# pressure.net
KiCad netlist of a schematic drawn in Altium Designer
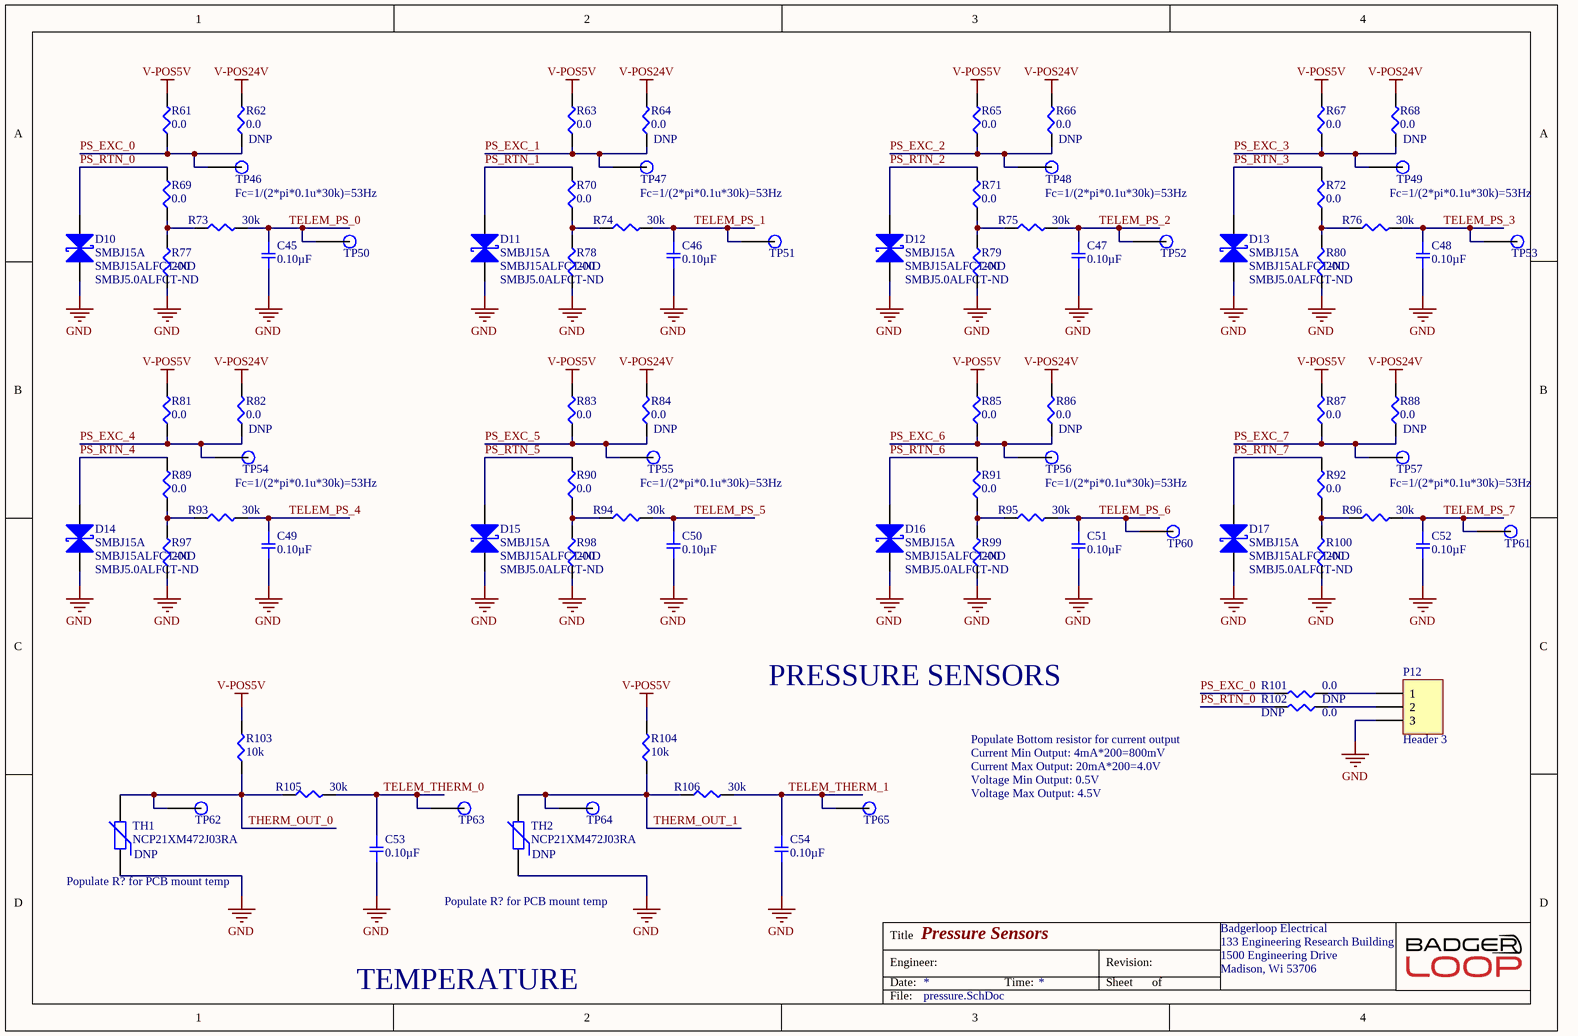
[diagram p0: pressure.SchDoc]

(export (version "E")
  (design (tool "Eeschema 10.0.6"))
  (components
    (comp (ref "C45")
      (value "0.10µF")
      (footprint "SMD-0805C")
      (description "CAP CER 0.1UF 25V X7R 0805")
      (fields
        (field (name "DIGI-KEY PART NUMBER") "490-12754-1-ND")
        (field (name "PART NUMBER") "GRM219R71E104KA01D")
      )
      (libsource (lib "capacitors") (part "GRM219R71E104KA01D"))
    )
    (comp (ref "C46")
      (value "0.10µF")
      (footprint "SMD-0805C")
      (description "CAP CER 0.1UF 25V X7R 0805")
      (fields
        (field (name "DIGI-KEY PART NUMBER") "490-12754-1-ND")
        (field (name "PART NUMBER") "GRM219R71E104KA01D")
      )
      (libsource (lib "capacitors") (part "GRM219R71E104KA01D"))
    )
    (comp (ref "C47")
      (value "0.10µF")
      (footprint "SMD-0805C")
      (description "CAP CER 0.1UF 25V X7R 0805")
      (fields
        (field (name "DIGI-KEY PART NUMBER") "490-12754-1-ND")
        (field (name "PART NUMBER") "GRM219R71E104KA01D")
      )
      (libsource (lib "capacitors") (part "GRM219R71E104KA01D"))
    )
    (comp (ref "C48")
      (value "0.10µF")
      (footprint "SMD-0805C")
      (description "CAP CER 0.1UF 25V X7R 0805")
      (fields
        (field (name "DIGI-KEY PART NUMBER") "490-12754-1-ND")
        (field (name "PART NUMBER") "GRM219R71E104KA01D")
      )
      (libsource (lib "capacitors") (part "GRM219R71E104KA01D"))
    )
    (comp (ref "C49")
      (value "0.10µF")
      (footprint "SMD-0805C")
      (description "CAP CER 0.1UF 25V X7R 0805")
      (fields
        (field (name "DIGI-KEY PART NUMBER") "490-12754-1-ND")
        (field (name "PART NUMBER") "GRM219R71E104KA01D")
      )
      (libsource (lib "capacitors") (part "GRM219R71E104KA01D"))
    )
    (comp (ref "C50")
      (value "0.10µF")
      (footprint "SMD-0805C")
      (description "CAP CER 0.1UF 25V X7R 0805")
      (fields
        (field (name "DIGI-KEY PART NUMBER") "490-12754-1-ND")
        (field (name "PART NUMBER") "GRM219R71E104KA01D")
      )
      (libsource (lib "capacitors") (part "GRM219R71E104KA01D"))
    )
    (comp (ref "C51")
      (value "0.10µF")
      (footprint "SMD-0805C")
      (description "CAP CER 0.1UF 25V X7R 0805")
      (fields
        (field (name "DIGI-KEY PART NUMBER") "490-12754-1-ND")
        (field (name "PART NUMBER") "GRM219R71E104KA01D")
      )
      (libsource (lib "capacitors") (part "GRM219R71E104KA01D"))
    )
    (comp (ref "C52")
      (value "0.10µF")
      (footprint "SMD-0805C")
      (description "CAP CER 0.1UF 25V X7R 0805")
      (fields
        (field (name "DIGI-KEY PART NUMBER") "490-12754-1-ND")
        (field (name "PART NUMBER") "GRM219R71E104KA01D")
      )
      (libsource (lib "capacitors") (part "GRM219R71E104KA01D"))
    )
    (comp (ref "C53")
      (value "0.10µF")
      (footprint "SMD-0805C")
      (description "CAP CER 0.1UF 16V X7R 0805")
      (fields
        (field (name "DIGI-KEY PART NUMBER") "490-1683-1-ND")
        (field (name "PART NUMBER") "GRM219R71C104KA01D")
      )
      (libsource (lib "capacitors") (part "GRM219R71C104KA01D"))
    )
    (comp (ref "C54")
      (value "0.10µF")
      (footprint "SMD-0805C")
      (description "CAP CER 0.1UF 16V X7R 0805")
      (fields
        (field (name "DIGI-KEY PART NUMBER") "490-1683-1-ND")
        (field (name "PART NUMBER") "GRM219R71C104KA01D")
      )
      (libsource (lib "capacitors") (part "GRM219R71C104KA01D"))
    )
    (comp (ref "D10")
      (value "SMBJ15A")
      (footprint "DIOM4436X26N")
      (description "TVS DIODE 5V 9.2V DO214AA")
      (fields
        (field (name "MANUFACTURER") "Littelfuse")
        (field (name "SUPPLIER PART NUMBER 1") "SMBJ15ALFCT-ND")
        (field (name "SUPPLIER PART NUMBER 2") "SMBJ5.0ALFCT-ND")
      )
      (libsource (lib "misc") (part "SMBJ15A"))
    )
    (comp (ref "D11")
      (value "SMBJ15A")
      (footprint "DIOM4436X26N")
      (description "TVS DIODE 5V 9.2V DO214AA")
      (fields
        (field (name "MANUFACTURER") "Littelfuse")
        (field (name "SUPPLIER PART NUMBER 1") "SMBJ15ALFCT-ND")
        (field (name "SUPPLIER PART NUMBER 2") "SMBJ5.0ALFCT-ND")
      )
      (libsource (lib "misc") (part "SMBJ15A"))
    )
    (comp (ref "D12")
      (value "SMBJ15A")
      (footprint "DIOM4436X26N")
      (description "TVS DIODE 5V 9.2V DO214AA")
      (fields
        (field (name "MANUFACTURER") "Littelfuse")
        (field (name "SUPPLIER PART NUMBER 1") "SMBJ15ALFCT-ND")
        (field (name "SUPPLIER PART NUMBER 2") "SMBJ5.0ALFCT-ND")
      )
      (libsource (lib "misc") (part "SMBJ15A"))
    )
    (comp (ref "D13")
      (value "SMBJ15A")
      (footprint "DIOM4436X26N")
      (description "TVS DIODE 5V 9.2V DO214AA")
      (fields
        (field (name "MANUFACTURER") "Littelfuse")
        (field (name "SUPPLIER PART NUMBER 1") "SMBJ15ALFCT-ND")
        (field (name "SUPPLIER PART NUMBER 2") "SMBJ5.0ALFCT-ND")
      )
      (libsource (lib "misc") (part "SMBJ15A"))
    )
    (comp (ref "D14")
      (value "SMBJ15A")
      (footprint "DIOM4436X26N")
      (description "TVS DIODE 5V 9.2V DO214AA")
      (fields
        (field (name "MANUFACTURER") "Littelfuse")
        (field (name "SUPPLIER PART NUMBER 1") "SMBJ15ALFCT-ND")
        (field (name "SUPPLIER PART NUMBER 2") "SMBJ5.0ALFCT-ND")
      )
      (libsource (lib "misc") (part "SMBJ15A"))
    )
    (comp (ref "D15")
      (value "SMBJ15A")
      (footprint "DIOM4436X26N")
      (description "TVS DIODE 5V 9.2V DO214AA")
      (fields
        (field (name "MANUFACTURER") "Littelfuse")
        (field (name "SUPPLIER PART NUMBER 1") "SMBJ15ALFCT-ND")
        (field (name "SUPPLIER PART NUMBER 2") "SMBJ5.0ALFCT-ND")
      )
      (libsource (lib "misc") (part "SMBJ15A"))
    )
    (comp (ref "D16")
      (value "SMBJ15A")
      (footprint "DIOM4436X26N")
      (description "TVS DIODE 5V 9.2V DO214AA")
      (fields
        (field (name "MANUFACTURER") "Littelfuse")
        (field (name "SUPPLIER PART NUMBER 1") "SMBJ15ALFCT-ND")
        (field (name "SUPPLIER PART NUMBER 2") "SMBJ5.0ALFCT-ND")
      )
      (libsource (lib "misc") (part "SMBJ15A"))
    )
    (comp (ref "D17")
      (value "SMBJ15A")
      (footprint "DIOM4436X26N")
      (description "TVS DIODE 5V 9.2V DO214AA")
      (fields
        (field (name "MANUFACTURER") "Littelfuse")
        (field (name "SUPPLIER PART NUMBER 1") "SMBJ15ALFCT-ND")
        (field (name "SUPPLIER PART NUMBER 2") "SMBJ5.0ALFCT-ND")
      )
      (libsource (lib "misc") (part "SMBJ15A"))
    )
    (comp (ref "P12")
      (value "Header 3")
      (footprint "Pin Header 1x3 TH Pitch 2.54mm")
      (description "Header, 3-Pin")
      (fields (field (name "PUBLISHER") "Altium Limited"))
      (libsource (lib "connector") (part "Header 3"))
    )
    (comp (ref "R61")
      (value "0.0")
      (footprint "SMD-0805-RES")
      (description "RES SMD 0.0 OHM JUMPER 1/8W 0805")
      (fields (field (name "PART NUMBER") "ERJ-6GEY0R00V") (field (name "DIGI-KEY PART NUMBER") "P0.0ACT-ND"))
      (libsource (lib "resistors") (part "ERJ-6GEY0R00V"))
    )
    (comp (ref "R62")
      (value "0.0")
      (footprint "SMD-0805-RES")
      (description "RES SMD 0.0 OHM JUMPER 1/8W 0805")
      (fields
        (field (name "PART NUMBER") "ERJ-6GEY0R00V")
        (field (name "DIGI-KEY PART NUMBER") "P0.0ACT-ND")
        (field (name "DNP") "DNP")
      )
      (libsource (lib "resistors") (part "ERJ-6GEY0R00V"))
    )
    (comp (ref "R63")
      (value "0.0")
      (footprint "SMD-0805-RES")
      (description "RES SMD 0.0 OHM JUMPER 1/8W 0805")
      (fields (field (name "PART NUMBER") "ERJ-6GEY0R00V") (field (name "DIGI-KEY PART NUMBER") "P0.0ACT-ND"))
      (libsource (lib "resistors") (part "ERJ-6GEY0R00V"))
    )
    (comp (ref "R64")
      (value "0.0")
      (footprint "SMD-0805-RES")
      (description "RES SMD 0.0 OHM JUMPER 1/8W 0805")
      (fields
        (field (name "PART NUMBER") "ERJ-6GEY0R00V")
        (field (name "DIGI-KEY PART NUMBER") "P0.0ACT-ND")
        (field (name "DNP") "DNP")
      )
      (libsource (lib "resistors") (part "ERJ-6GEY0R00V"))
    )
    (comp (ref "R65")
      (value "0.0")
      (footprint "SMD-0805-RES")
      (description "RES SMD 0.0 OHM JUMPER 1/8W 0805")
      (fields (field (name "PART NUMBER") "ERJ-6GEY0R00V") (field (name "DIGI-KEY PART NUMBER") "P0.0ACT-ND"))
      (libsource (lib "resistors") (part "ERJ-6GEY0R00V"))
    )
    (comp (ref "R66")
      (value "0.0")
      (footprint "SMD-0805-RES")
      (description "RES SMD 0.0 OHM JUMPER 1/8W 0805")
      (fields
        (field (name "PART NUMBER") "ERJ-6GEY0R00V")
        (field (name "DIGI-KEY PART NUMBER") "P0.0ACT-ND")
        (field (name "DNP") "DNP")
      )
      (libsource (lib "resistors") (part "ERJ-6GEY0R00V"))
    )
    (comp (ref "R67")
      (value "0.0")
      (footprint "SMD-0805-RES")
      (description "RES SMD 0.0 OHM JUMPER 1/8W 0805")
      (fields (field (name "PART NUMBER") "ERJ-6GEY0R00V") (field (name "DIGI-KEY PART NUMBER") "P0.0ACT-ND"))
      (libsource (lib "resistors") (part "ERJ-6GEY0R00V"))
    )
    (comp (ref "R68")
      (value "0.0")
      (footprint "SMD-0805-RES")
      (description "RES SMD 0.0 OHM JUMPER 1/8W 0805")
      (fields
        (field (name "PART NUMBER") "ERJ-6GEY0R00V")
        (field (name "DIGI-KEY PART NUMBER") "P0.0ACT-ND")
        (field (name "DNP") "DNP")
      )
      (libsource (lib "resistors") (part "ERJ-6GEY0R00V"))
    )
    (comp (ref "R69")
      (value "0.0")
      (footprint "SMD-0805-RES")
      (description "RES SMD 0.0 OHM JUMPER 1/8W 0805")
      (fields (field (name "PART NUMBER") "ERJ-6GEY0R00V") (field (name "DIGI-KEY PART NUMBER") "P0.0ACT-ND"))
      (libsource (lib "resistors") (part "ERJ-6GEY0R00V"))
    )
    (comp (ref "R70")
      (value "0.0")
      (footprint "SMD-0805-RES")
      (description "RES SMD 0.0 OHM JUMPER 1/8W 0805")
      (fields (field (name "PART NUMBER") "ERJ-6GEY0R00V") (field (name "DIGI-KEY PART NUMBER") "P0.0ACT-ND"))
      (libsource (lib "resistors") (part "ERJ-6GEY0R00V"))
    )
    (comp (ref "R71")
      (value "0.0")
      (footprint "SMD-0805-RES")
      (description "RES SMD 0.0 OHM JUMPER 1/8W 0805")
      (fields (field (name "PART NUMBER") "ERJ-6GEY0R00V") (field (name "DIGI-KEY PART NUMBER") "P0.0ACT-ND"))
      (libsource (lib "resistors") (part "ERJ-6GEY0R00V"))
    )
    (comp (ref "R72")
      (value "0.0")
      (footprint "SMD-0805-RES")
      (description "RES SMD 0.0 OHM JUMPER 1/8W 0805")
      (fields (field (name "PART NUMBER") "ERJ-6GEY0R00V") (field (name "DIGI-KEY PART NUMBER") "P0.0ACT-ND"))
      (libsource (lib "resistors") (part "ERJ-6GEY0R00V"))
    )
    (comp (ref "R73")
      (value "30k")
      (footprint "SMD-0805-RES")
      (description "RES SMD 30K OHM 1% 1/8W 0805")
      (fields
        (field (name "PART NUMBER") "ERJ-6ENF3002V")
        (field (name "DIGI-KEY PART NUMBER") "P30.0KCCT-ND")
      )
      (libsource (lib "resistors") (part "ERJ-6ENF3002V"))
    )
    (comp (ref "R74")
      (value "30k")
      (footprint "SMD-0805-RES")
      (description "RES SMD 30K OHM 1% 1/8W 0805")
      (fields
        (field (name "PART NUMBER") "ERJ-6ENF3002V")
        (field (name "DIGI-KEY PART NUMBER") "P30.0KCCT-ND")
      )
      (libsource (lib "resistors") (part "ERJ-6ENF3002V"))
    )
    (comp (ref "R75")
      (value "30k")
      (footprint "SMD-0805-RES")
      (description "RES SMD 30K OHM 1% 1/8W 0805")
      (fields
        (field (name "PART NUMBER") "ERJ-6ENF3002V")
        (field (name "DIGI-KEY PART NUMBER") "P30.0KCCT-ND")
      )
      (libsource (lib "resistors") (part "ERJ-6ENF3002V"))
    )
    (comp (ref "R76")
      (value "30k")
      (footprint "SMD-0805-RES")
      (description "RES SMD 30K OHM 1% 1/8W 0805")
      (fields
        (field (name "PART NUMBER") "ERJ-6ENF3002V")
        (field (name "DIGI-KEY PART NUMBER") "P30.0KCCT-ND")
      )
      (libsource (lib "resistors") (part "ERJ-6ENF3002V"))
    )
    (comp (ref "R77")
      (value "200")
      (footprint "SMD-0805-RES")
      (description "RES SMD 200 OHM 1% 1/2W 0805")
      (fields
        (field (name "PART NUMBER") "ERJ-P06F2000V")
        (field (name "DIGI-KEY PART NUMBER") "P16064CT-ND")
      )
      (libsource (lib "resistors") (part "ERJ-P06F2000V"))
    )
    (comp (ref "R78")
      (value "200")
      (footprint "SMD-0805-RES")
      (description "RES SMD 200 OHM 1% 1/2W 0805")
      (fields
        (field (name "PART NUMBER") "ERJ-P06F2000V")
        (field (name "DIGI-KEY PART NUMBER") "P16064CT-ND")
      )
      (libsource (lib "resistors") (part "ERJ-P06F2000V"))
    )
    (comp (ref "R79")
      (value "200")
      (footprint "SMD-0805-RES")
      (description "RES SMD 200 OHM 1% 1/2W 0805")
      (fields
        (field (name "PART NUMBER") "ERJ-P06F2000V")
        (field (name "DIGI-KEY PART NUMBER") "P16064CT-ND")
      )
      (libsource (lib "resistors") (part "ERJ-P06F2000V"))
    )
    (comp (ref "R80")
      (value "200")
      (footprint "SMD-0805-RES")
      (description "RES SMD 200 OHM 1% 1/2W 0805")
      (fields
        (field (name "PART NUMBER") "ERJ-P06F2000V")
        (field (name "DIGI-KEY PART NUMBER") "P16064CT-ND")
      )
      (libsource (lib "resistors") (part "ERJ-P06F2000V"))
    )
    (comp (ref "R81")
      (value "0.0")
      (footprint "SMD-0805-RES")
      (description "RES SMD 0.0 OHM JUMPER 1/8W 0805")
      (fields (field (name "PART NUMBER") "ERJ-6GEY0R00V") (field (name "DIGI-KEY PART NUMBER") "P0.0ACT-ND"))
      (libsource (lib "resistors") (part "ERJ-6GEY0R00V"))
    )
    (comp (ref "R82")
      (value "0.0")
      (footprint "SMD-0805-RES")
      (description "RES SMD 0.0 OHM JUMPER 1/8W 0805")
      (fields
        (field (name "PART NUMBER") "ERJ-6GEY0R00V")
        (field (name "DIGI-KEY PART NUMBER") "P0.0ACT-ND")
        (field (name "DNP") "DNP")
      )
      (libsource (lib "resistors") (part "ERJ-6GEY0R00V"))
    )
    (comp (ref "R83")
      (value "0.0")
      (footprint "SMD-0805-RES")
      (description "RES SMD 0.0 OHM JUMPER 1/8W 0805")
      (fields (field (name "PART NUMBER") "ERJ-6GEY0R00V") (field (name "DIGI-KEY PART NUMBER") "P0.0ACT-ND"))
      (libsource (lib "resistors") (part "ERJ-6GEY0R00V"))
    )
    (comp (ref "R84")
      (value "0.0")
      (footprint "SMD-0805-RES")
      (description "RES SMD 0.0 OHM JUMPER 1/8W 0805")
      (fields
        (field (name "PART NUMBER") "ERJ-6GEY0R00V")
        (field (name "DIGI-KEY PART NUMBER") "P0.0ACT-ND")
        (field (name "DNP") "DNP")
      )
      (libsource (lib "resistors") (part "ERJ-6GEY0R00V"))
    )
    (comp (ref "R85")
      (value "0.0")
      (footprint "SMD-0805-RES")
      (description "RES SMD 0.0 OHM JUMPER 1/8W 0805")
      (fields (field (name "PART NUMBER") "ERJ-6GEY0R00V") (field (name "DIGI-KEY PART NUMBER") "P0.0ACT-ND"))
      (libsource (lib "resistors") (part "ERJ-6GEY0R00V"))
    )
    (comp (ref "R86")
      (value "0.0")
      (footprint "SMD-0805-RES")
      (description "RES SMD 0.0 OHM JUMPER 1/8W 0805")
      (fields
        (field (name "PART NUMBER") "ERJ-6GEY0R00V")
        (field (name "DIGI-KEY PART NUMBER") "P0.0ACT-ND")
        (field (name "DNP") "DNP")
      )
      (libsource (lib "resistors") (part "ERJ-6GEY0R00V"))
    )
    (comp (ref "R87")
      (value "0.0")
      (footprint "SMD-0805-RES")
      (description "RES SMD 0.0 OHM JUMPER 1/8W 0805")
      (fields (field (name "PART NUMBER") "ERJ-6GEY0R00V") (field (name "DIGI-KEY PART NUMBER") "P0.0ACT-ND"))
      (libsource (lib "resistors") (part "ERJ-6GEY0R00V"))
    )
    (comp (ref "R88")
      (value "0.0")
      (footprint "SMD-0805-RES")
      (description "RES SMD 0.0 OHM JUMPER 1/8W 0805")
      (fields
        (field (name "PART NUMBER") "ERJ-6GEY0R00V")
        (field (name "DIGI-KEY PART NUMBER") "P0.0ACT-ND")
        (field (name "DNP") "DNP")
      )
      (libsource (lib "resistors") (part "ERJ-6GEY0R00V"))
    )
    (comp (ref "R89")
      (value "0.0")
      (footprint "SMD-0805-RES")
      (description "RES SMD 0.0 OHM JUMPER 1/8W 0805")
      (fields (field (name "PART NUMBER") "ERJ-6GEY0R00V") (field (name "DIGI-KEY PART NUMBER") "P0.0ACT-ND"))
      (libsource (lib "resistors") (part "ERJ-6GEY0R00V"))
    )
    (comp (ref "R90")
      (value "0.0")
      (footprint "SMD-0805-RES")
      (description "RES SMD 0.0 OHM JUMPER 1/8W 0805")
      (fields (field (name "PART NUMBER") "ERJ-6GEY0R00V") (field (name "DIGI-KEY PART NUMBER") "P0.0ACT-ND"))
      (libsource (lib "resistors") (part "ERJ-6GEY0R00V"))
    )
    (comp (ref "R91")
      (value "0.0")
      (footprint "SMD-0805-RES")
      (description "RES SMD 0.0 OHM JUMPER 1/8W 0805")
      (fields (field (name "PART NUMBER") "ERJ-6GEY0R00V") (field (name "DIGI-KEY PART NUMBER") "P0.0ACT-ND"))
      (libsource (lib "resistors") (part "ERJ-6GEY0R00V"))
    )
    (comp (ref "R92")
      (value "0.0")
      (footprint "SMD-0805-RES")
      (description "RES SMD 0.0 OHM JUMPER 1/8W 0805")
      (fields (field (name "PART NUMBER") "ERJ-6GEY0R00V") (field (name "DIGI-KEY PART NUMBER") "P0.0ACT-ND"))
      (libsource (lib "resistors") (part "ERJ-6GEY0R00V"))
    )
    (comp (ref "R93")
      (value "30k")
      (footprint "SMD-0805-RES")
      (description "RES SMD 30K OHM 1% 1/8W 0805")
      (fields
        (field (name "PART NUMBER") "ERJ-6ENF3002V")
        (field (name "DIGI-KEY PART NUMBER") "P30.0KCCT-ND")
      )
      (libsource (lib "resistors") (part "ERJ-6ENF3002V"))
    )
    (comp (ref "R94")
      (value "30k")
      (footprint "SMD-0805-RES")
      (description "RES SMD 30K OHM 1% 1/8W 0805")
      (fields
        (field (name "PART NUMBER") "ERJ-6ENF3002V")
        (field (name "DIGI-KEY PART NUMBER") "P30.0KCCT-ND")
      )
      (libsource (lib "resistors") (part "ERJ-6ENF3002V"))
    )
    (comp (ref "R95")
      (value "30k")
      (footprint "SMD-0805-RES")
      (description "RES SMD 30K OHM 1% 1/8W 0805")
      (fields
        (field (name "PART NUMBER") "ERJ-6ENF3002V")
        (field (name "DIGI-KEY PART NUMBER") "P30.0KCCT-ND")
      )
      (libsource (lib "resistors") (part "ERJ-6ENF3002V"))
    )
    (comp (ref "R96")
      (value "30k")
      (footprint "SMD-0805-RES")
      (description "RES SMD 30K OHM 1% 1/8W 0805")
      (fields
        (field (name "PART NUMBER") "ERJ-6ENF3002V")
        (field (name "DIGI-KEY PART NUMBER") "P30.0KCCT-ND")
      )
      (libsource (lib "resistors") (part "ERJ-6ENF3002V"))
    )
    (comp (ref "R97")
      (value "200")
      (footprint "SMD-0805-RES")
      (description "RES SMD 200 OHM 1% 1/2W 0805")
      (fields
        (field (name "PART NUMBER") "ERJ-P06F2000V")
        (field (name "DIGI-KEY PART NUMBER") "P16064CT-ND")
      )
      (libsource (lib "resistors") (part "ERJ-P06F2000V"))
    )
    (comp (ref "R98")
      (value "200")
      (footprint "SMD-0805-RES")
      (description "RES SMD 200 OHM 1% 1/2W 0805")
      (fields
        (field (name "PART NUMBER") "ERJ-P06F2000V")
        (field (name "DIGI-KEY PART NUMBER") "P16064CT-ND")
      )
      (libsource (lib "resistors") (part "ERJ-P06F2000V"))
    )
    (comp (ref "R99")
      (value "200")
      (footprint "SMD-0805-RES")
      (description "RES SMD 200 OHM 1% 1/2W 0805")
      (fields
        (field (name "PART NUMBER") "ERJ-P06F2000V")
        (field (name "DIGI-KEY PART NUMBER") "P16064CT-ND")
      )
      (libsource (lib "resistors") (part "ERJ-P06F2000V"))
    )
    (comp (ref "R100")
      (value "200")
      (footprint "SMD-0805-RES")
      (description "RES SMD 200 OHM 1% 1/2W 0805")
      (fields
        (field (name "PART NUMBER") "ERJ-P06F2000V")
        (field (name "DIGI-KEY PART NUMBER") "P16064CT-ND")
      )
      (libsource (lib "resistors") (part "ERJ-P06F2000V"))
    )
    (comp (ref "R101")
      (value "0.0")
      (footprint "SMD-0805-RES")
      (description "RES SMD 0.0 OHM JUMPER 1/8W 0805")
      (fields
        (field (name "PART NUMBER") "ERJ-6GEY0R00V")
        (field (name "DIGI-KEY PART NUMBER") "P0.0ACT-ND")
        (field (name "DNP") "DNP")
      )
      (libsource (lib "resistors") (part "ERJ-6GEY0R00V"))
    )
    (comp (ref "R102")
      (value "0.0")
      (footprint "SMD-0805-RES")
      (description "RES SMD 0.0 OHM JUMPER 1/8W 0805")
      (fields
        (field (name "PART NUMBER") "ERJ-6GEY0R00V")
        (field (name "DIGI-KEY PART NUMBER") "P0.0ACT-ND")
        (field (name "DNP") "DNP")
      )
      (libsource (lib "resistors") (part "ERJ-6GEY0R00V"))
    )
    (comp (ref "R103")
      (value "10k")
      (footprint "SMD-0805-RES")
      (description "RES SMD 10K OHM 1% 1/2W 0805")
      (fields
        (field (name "PART NUMBER") "ERJ-P06F1002V")
        (field (name "DIGI-KEY PART NUMBER") "P16059CT-ND")
      )
      (libsource (lib "resistors") (part "ERJ-P06F1002V"))
    )
    (comp (ref "R104")
      (value "10k")
      (footprint "SMD-0805-RES")
      (description "RES SMD 10K OHM 1% 1/2W 0805")
      (fields
        (field (name "PART NUMBER") "ERJ-P06F1002V")
        (field (name "DIGI-KEY PART NUMBER") "P16059CT-ND")
      )
      (libsource (lib "resistors") (part "ERJ-P06F1002V"))
    )
    (comp (ref "R105")
      (value "30k")
      (footprint "SMD-0805-RES")
      (description "RES SMD 30K OHM 1% 1/8W 0805")
      (fields
        (field (name "PART NUMBER") "ERJ-6ENF3002V")
        (field (name "DIGI-KEY PART NUMBER") "P30.0KCCT-ND")
      )
      (libsource (lib "resistors") (part "ERJ-6ENF3002V"))
    )
    (comp (ref "R106")
      (value "30k")
      (footprint "SMD-0805-RES")
      (description "RES SMD 30K OHM 1% 1/8W 0805")
      (fields
        (field (name "PART NUMBER") "ERJ-6ENF3002V")
        (field (name "DIGI-KEY PART NUMBER") "P30.0KCCT-ND")
      )
      (libsource (lib "resistors") (part "ERJ-6ENF3002V"))
    )
    (comp (ref "TH1")
      (value "NCP21XM472J03RA")
      (footprint "SMD-0805-RES")
      (description "NTC THERMISTOR 4.7K OHM 5% 0805")
      (fields
        (field (name "MANUFACTURER") "Murata")
        (field (name "TOLERANCE") "5%")
        (field (name "DNP") "DNP")
      )
      (libsource (lib "misc") (part "NCP21XM472J03RA"))
    )
    (comp (ref "TH2")
      (value "NCP21XM472J03RA")
      (footprint "SMD-0805-RES")
      (description "NTC THERMISTOR 4.7K OHM 5% 0805")
      (fields
        (field (name "MANUFACTURER") "Murata")
        (field (name "TOLERANCE") "5%")
        (field (name "DNP") "DNP")
      )
      (libsource (lib "misc") (part "NCP21XM472J03RA"))
    )
    (comp (ref "TP46")
      (value "TP")
      (footprint "Test Point")
      (description "SMD TEST POINT")
      (libsource (lib "misc") (part "TP"))
    )
    (comp (ref "TP47")
      (value "TP")
      (footprint "Test Point")
      (description "SMD TEST POINT")
      (libsource (lib "misc") (part "TP"))
    )
    (comp (ref "TP48")
      (value "TP")
      (footprint "Test Point")
      (description "SMD TEST POINT")
      (libsource (lib "misc") (part "TP"))
    )
    (comp (ref "TP49")
      (value "TP")
      (footprint "Test Point")
      (description "SMD TEST POINT")
      (libsource (lib "misc") (part "TP"))
    )
    (comp (ref "TP50")
      (value "TP")
      (footprint "Test Point")
      (description "SMD TEST POINT")
      (libsource (lib "misc") (part "TP"))
    )
    (comp (ref "TP51")
      (value "TP")
      (footprint "Test Point")
      (description "SMD TEST POINT")
      (libsource (lib "misc") (part "TP"))
    )
    (comp (ref "TP52")
      (value "TP")
      (footprint "Test Point")
      (description "SMD TEST POINT")
      (libsource (lib "misc") (part "TP"))
    )
    (comp (ref "TP53")
      (value "TP")
      (footprint "Test Point")
      (description "SMD TEST POINT")
      (libsource (lib "misc") (part "TP"))
    )
    (comp (ref "TP54")
      (value "TP")
      (footprint "Test Point")
      (description "SMD TEST POINT")
      (libsource (lib "misc") (part "TP"))
    )
    (comp (ref "TP55")
      (value "TP")
      (footprint "Test Point")
      (description "SMD TEST POINT")
      (libsource (lib "misc") (part "TP"))
    )
    (comp (ref "TP56")
      (value "TP")
      (footprint "Test Point")
      (description "SMD TEST POINT")
      (libsource (lib "misc") (part "TP"))
    )
    (comp (ref "TP57")
      (value "TP")
      (footprint "Test Point")
      (description "SMD TEST POINT")
      (libsource (lib "misc") (part "TP"))
    )
    (comp (ref "TP60")
      (value "TP")
      (footprint "Test Point")
      (description "SMD TEST POINT")
      (libsource (lib "misc") (part "TP"))
    )
    (comp (ref "TP61")
      (value "TP")
      (footprint "Test Point")
      (description "SMD TEST POINT")
      (libsource (lib "misc") (part "TP"))
    )
    (comp (ref "TP62")
      (value "TP")
      (footprint "Test Point")
      (description "SMD TEST POINT")
      (libsource (lib "misc") (part "TP"))
    )
    (comp (ref "TP63")
      (value "TP")
      (footprint "Test Point")
      (description "SMD TEST POINT")
      (libsource (lib "misc") (part "TP"))
    )
    (comp (ref "TP64")
      (value "TP")
      (footprint "Test Point")
      (description "SMD TEST POINT")
      (libsource (lib "misc") (part "TP"))
    )
    (comp (ref "TP65")
      (value "TP")
      (footprint "Test Point")
      (description "SMD TEST POINT")
      (libsource (lib "misc") (part "TP"))
    )
  )
  (nets
    (net (code "1") (name "/PS_EXC_0") (class "Default")
      (node (ref "R101") (pin "2") (pinfunction "2_2") (pintype "passive"))
      (node (ref "R61") (pin "1") (pinfunction "1_1") (pintype "passive"))
      (node (ref "R62") (pin "1") (pinfunction "1_1") (pintype "passive"))
      (node (ref "TP46") (pin "1") (pinfunction "1_1") (pintype "passive"))
    )
    (net (code "2") (name "/PS_EXC_1") (class "Default")
      (node (ref "R63") (pin "1") (pinfunction "1_1") (pintype "passive"))
      (node (ref "R64") (pin "1") (pinfunction "1_1") (pintype "passive"))
      (node (ref "TP47") (pin "1") (pinfunction "1_1") (pintype "passive"))
    )
    (net (code "3") (name "/PS_EXC_2") (class "Default")
      (node (ref "R65") (pin "1") (pinfunction "1_1") (pintype "passive"))
      (node (ref "R66") (pin "1") (pinfunction "1_1") (pintype "passive"))
      (node (ref "TP48") (pin "1") (pinfunction "1_1") (pintype "passive"))
    )
    (net (code "4") (name "/PS_EXC_3") (class "Default")
      (node (ref "R67") (pin "1") (pinfunction "1_1") (pintype "passive"))
      (node (ref "R68") (pin "1") (pinfunction "1_1") (pintype "passive"))
      (node (ref "TP49") (pin "1") (pinfunction "1_1") (pintype "passive"))
    )
    (net (code "5") (name "/PS_EXC_4") (class "Default")
      (node (ref "R81") (pin "1") (pinfunction "1_1") (pintype "passive"))
      (node (ref "R82") (pin "1") (pinfunction "1_1") (pintype "passive"))
      (node (ref "TP54") (pin "1") (pinfunction "1_1") (pintype "passive"))
    )
    (net (code "6") (name "/PS_EXC_5") (class "Default")
      (node (ref "R83") (pin "1") (pinfunction "1_1") (pintype "passive"))
      (node (ref "R84") (pin "1") (pinfunction "1_1") (pintype "passive"))
      (node (ref "TP55") (pin "1") (pinfunction "1_1") (pintype "passive"))
    )
    (net (code "7") (name "/PS_EXC_6") (class "Default")
      (node (ref "R85") (pin "1") (pinfunction "1_1") (pintype "passive"))
      (node (ref "R86") (pin "1") (pinfunction "1_1") (pintype "passive"))
      (node (ref "TP56") (pin "1") (pinfunction "1_1") (pintype "passive"))
    )
    (net (code "8") (name "/PS_EXC_7") (class "Default")
      (node (ref "R87") (pin "1") (pinfunction "1_1") (pintype "passive"))
      (node (ref "R88") (pin "1") (pinfunction "1_1") (pintype "passive"))
      (node (ref "TP57") (pin "1") (pinfunction "1_1") (pintype "passive"))
    )
    (net (code "9") (name "/PS_RTN_0") (class "Default")
      (node (ref "D10") (pin "2") (pinfunction "K_2") (pintype "passive"))
      (node (ref "R102") (pin "2") (pinfunction "2_2") (pintype "passive"))
      (node (ref "R69") (pin "2") (pinfunction "2_2") (pintype "passive"))
    )
    (net (code "10") (name "/PS_RTN_1") (class "Default")
      (node (ref "D11") (pin "2") (pinfunction "K_2") (pintype "passive"))
      (node (ref "R70") (pin "2") (pinfunction "2_2") (pintype "passive"))
    )
    (net (code "11") (name "/PS_RTN_2") (class "Default")
      (node (ref "D12") (pin "2") (pinfunction "K_2") (pintype "passive"))
      (node (ref "R71") (pin "2") (pinfunction "2_2") (pintype "passive"))
    )
    (net (code "12") (name "/PS_RTN_3") (class "Default")
      (node (ref "D13") (pin "2") (pinfunction "K_2") (pintype "passive"))
      (node (ref "R72") (pin "2") (pinfunction "2_2") (pintype "passive"))
    )
    (net (code "13") (name "/PS_RTN_4") (class "Default")
      (node (ref "D14") (pin "2") (pinfunction "K_2") (pintype "passive"))
      (node (ref "R89") (pin "2") (pinfunction "2_2") (pintype "passive"))
    )
    (net (code "14") (name "/PS_RTN_5") (class "Default")
      (node (ref "D15") (pin "2") (pinfunction "K_2") (pintype "passive"))
      (node (ref "R90") (pin "2") (pinfunction "2_2") (pintype "passive"))
    )
    (net (code "15") (name "/PS_RTN_6") (class "Default")
      (node (ref "D16") (pin "2") (pinfunction "K_2") (pintype "passive"))
      (node (ref "R91") (pin "2") (pinfunction "2_2") (pintype "passive"))
    )
    (net (code "16") (name "/PS_RTN_7") (class "Default")
      (node (ref "D17") (pin "2") (pinfunction "K_2") (pintype "passive"))
      (node (ref "R92") (pin "2") (pinfunction "2_2") (pintype "passive"))
    )
    (net (code "17") (name "/TELEM_PS_0") (class "Default")
      (node (ref "C45") (pin "1") (pinfunction "1_1") (pintype "passive"))
      (node (ref "R73") (pin "2") (pinfunction "2_2") (pintype "passive"))
      (node (ref "TP50") (pin "1") (pinfunction "1_1") (pintype "passive"))
    )
    (net (code "18") (name "/TELEM_PS_1") (class "Default")
      (node (ref "C46") (pin "1") (pinfunction "1_1") (pintype "passive"))
      (node (ref "R74") (pin "2") (pinfunction "2_2") (pintype "passive"))
      (node (ref "TP51") (pin "1") (pinfunction "1_1") (pintype "passive"))
    )
    (net (code "19") (name "/TELEM_PS_2") (class "Default")
      (node (ref "C47") (pin "1") (pinfunction "1_1") (pintype "passive"))
      (node (ref "R75") (pin "2") (pinfunction "2_2") (pintype "passive"))
      (node (ref "TP52") (pin "1") (pinfunction "1_1") (pintype "passive"))
    )
    (net (code "20") (name "/TELEM_PS_3") (class "Default")
      (node (ref "C48") (pin "1") (pinfunction "1_1") (pintype "passive"))
      (node (ref "R76") (pin "2") (pinfunction "2_2") (pintype "passive"))
      (node (ref "TP53") (pin "1") (pinfunction "1_1") (pintype "passive"))
    )
    (net (code "21") (name "/TELEM_PS_4") (class "Default")
      (node (ref "C49") (pin "1") (pinfunction "1_1") (pintype "passive"))
      (node (ref "R93") (pin "2") (pinfunction "2_2") (pintype "passive"))
    )
    (net (code "22") (name "/TELEM_PS_5") (class "Default")
      (node (ref "C50") (pin "1") (pinfunction "1_1") (pintype "passive"))
      (node (ref "R94") (pin "2") (pinfunction "2_2") (pintype "passive"))
    )
    (net (code "23") (name "/TELEM_PS_6") (class "Default")
      (node (ref "C51") (pin "1") (pinfunction "1_1") (pintype "passive"))
      (node (ref "R95") (pin "2") (pinfunction "2_2") (pintype "passive"))
      (node (ref "TP60") (pin "1") (pinfunction "1_1") (pintype "passive"))
    )
    (net (code "24") (name "/TELEM_PS_7") (class "Default")
      (node (ref "C52") (pin "1") (pinfunction "1_1") (pintype "passive"))
      (node (ref "R96") (pin "2") (pinfunction "2_2") (pintype "passive"))
      (node (ref "TP61") (pin "1") (pinfunction "1_1") (pintype "passive"))
    )
    (net (code "25") (name "/TELEM_THERM_0") (class "Default")
      (node (ref "C53") (pin "1") (pinfunction "1_1") (pintype "passive"))
      (node (ref "R105") (pin "2") (pinfunction "2_2") (pintype "passive"))
      (node (ref "TP63") (pin "1") (pinfunction "1_1") (pintype "passive"))
    )
    (net (code "26") (name "/TELEM_THERM_1") (class "Default")
      (node (ref "C54") (pin "1") (pinfunction "1_1") (pintype "passive"))
      (node (ref "R106") (pin "2") (pinfunction "2_2") (pintype "passive"))
      (node (ref "TP65") (pin "1") (pinfunction "1_1") (pintype "passive"))
    )
    (net (code "27") (name "/THERM_OUT_0") (class "Default")
      (node (ref "R103") (pin "1") (pinfunction "1_1") (pintype "passive"))
      (node (ref "R105") (pin "1") (pinfunction "1_1") (pintype "passive"))
      (node (ref "TH1") (pin "2") (pinfunction "2_2") (pintype "passive"))
      (node (ref "TP62") (pin "1") (pinfunction "1_1") (pintype "passive"))
    )
    (net (code "28") (name "/THERM_OUT_1") (class "Default")
      (node (ref "R104") (pin "1") (pinfunction "1_1") (pintype "passive"))
      (node (ref "R106") (pin "1") (pinfunction "1_1") (pintype "passive"))
      (node (ref "TH2") (pin "2") (pinfunction "2_2") (pintype "passive"))
      (node (ref "TP64") (pin "1") (pinfunction "1_1") (pintype "passive"))
    )
    (net (code "29") (name "GND") (class "Default")
      (node (ref "C45") (pin "2") (pinfunction "2_2") (pintype "passive"))
      (node (ref "C46") (pin "2") (pinfunction "2_2") (pintype "passive"))
      (node (ref "C47") (pin "2") (pinfunction "2_2") (pintype "passive"))
      (node (ref "C48") (pin "2") (pinfunction "2_2") (pintype "passive"))
      (node (ref "C49") (pin "2") (pinfunction "2_2") (pintype "passive"))
      (node (ref "C50") (pin "2") (pinfunction "2_2") (pintype "passive"))
      (node (ref "C51") (pin "2") (pinfunction "2_2") (pintype "passive"))
      (node (ref "C52") (pin "2") (pinfunction "2_2") (pintype "passive"))
      (node (ref "C53") (pin "2") (pinfunction "2_2") (pintype "passive"))
      (node (ref "C54") (pin "2") (pinfunction "2_2") (pintype "passive"))
      (node (ref "D10") (pin "1") (pinfunction "A_1") (pintype "passive"))
      (node (ref "D11") (pin "1") (pinfunction "A_1") (pintype "passive"))
      (node (ref "D12") (pin "1") (pinfunction "A_1") (pintype "passive"))
      (node (ref "D13") (pin "1") (pinfunction "A_1") (pintype "passive"))
      (node (ref "D14") (pin "1") (pinfunction "A_1") (pintype "passive"))
      (node (ref "D15") (pin "1") (pinfunction "A_1") (pintype "passive"))
      (node (ref "D16") (pin "1") (pinfunction "A_1") (pintype "passive"))
      (node (ref "D17") (pin "1") (pinfunction "A_1") (pintype "passive"))
      (node (ref "P12") (pin "3") (pinfunction "3_3") (pintype "passive"))
      (node (ref "R100") (pin "1") (pinfunction "1_1") (pintype "passive"))
      (node (ref "R77") (pin "1") (pinfunction "1_1") (pintype "passive"))
      (node (ref "R78") (pin "1") (pinfunction "1_1") (pintype "passive"))
      (node (ref "R79") (pin "1") (pinfunction "1_1") (pintype "passive"))
      (node (ref "R80") (pin "1") (pinfunction "1_1") (pintype "passive"))
      (node (ref "R97") (pin "1") (pinfunction "1_1") (pintype "passive"))
      (node (ref "R98") (pin "1") (pinfunction "1_1") (pintype "passive"))
      (node (ref "R99") (pin "1") (pinfunction "1_1") (pintype "passive"))
      (node (ref "TH1") (pin "1") (pinfunction "1_1") (pintype "passive"))
      (node (ref "TH2") (pin "1") (pinfunction "1_1") (pintype "passive"))
    )
    (net (code "30") (name "Net-(P12-Pad1)") (class "Default")
      (node (ref "P12") (pin "1") (pinfunction "1_1") (pintype "passive"))
      (node (ref "R101") (pin "1") (pinfunction "1_1") (pintype "passive"))
    )
    (net (code "31") (name "Net-(P12-Pad2)") (class "Default")
      (node (ref "P12") (pin "2") (pinfunction "2_2") (pintype "passive"))
      (node (ref "R102") (pin "1") (pinfunction "1_1") (pintype "passive"))
    )
    (net (code "32") (name "Net-(R69-Pad1)") (class "Default")
      (node (ref "R69") (pin "1") (pinfunction "1_1") (pintype "passive"))
      (node (ref "R73") (pin "1") (pinfunction "1_1") (pintype "passive"))
      (node (ref "R77") (pin "2") (pinfunction "2_2") (pintype "passive"))
    )
    (net (code "33") (name "Net-(R70-Pad1)") (class "Default")
      (node (ref "R70") (pin "1") (pinfunction "1_1") (pintype "passive"))
      (node (ref "R74") (pin "1") (pinfunction "1_1") (pintype "passive"))
      (node (ref "R78") (pin "2") (pinfunction "2_2") (pintype "passive"))
    )
    (net (code "34") (name "Net-(R71-Pad1)") (class "Default")
      (node (ref "R71") (pin "1") (pinfunction "1_1") (pintype "passive"))
      (node (ref "R75") (pin "1") (pinfunction "1_1") (pintype "passive"))
      (node (ref "R79") (pin "2") (pinfunction "2_2") (pintype "passive"))
    )
    (net (code "35") (name "Net-(R72-Pad1)") (class "Default")
      (node (ref "R72") (pin "1") (pinfunction "1_1") (pintype "passive"))
      (node (ref "R76") (pin "1") (pinfunction "1_1") (pintype "passive"))
      (node (ref "R80") (pin "2") (pinfunction "2_2") (pintype "passive"))
    )
    (net (code "36") (name "Net-(R89-Pad1)") (class "Default")
      (node (ref "R89") (pin "1") (pinfunction "1_1") (pintype "passive"))
      (node (ref "R93") (pin "1") (pinfunction "1_1") (pintype "passive"))
      (node (ref "R97") (pin "2") (pinfunction "2_2") (pintype "passive"))
    )
    (net (code "37") (name "Net-(R90-Pad1)") (class "Default")
      (node (ref "R90") (pin "1") (pinfunction "1_1") (pintype "passive"))
      (node (ref "R94") (pin "1") (pinfunction "1_1") (pintype "passive"))
      (node (ref "R98") (pin "2") (pinfunction "2_2") (pintype "passive"))
    )
    (net (code "38") (name "Net-(R91-Pad1)") (class "Default")
      (node (ref "R91") (pin "1") (pinfunction "1_1") (pintype "passive"))
      (node (ref "R95") (pin "1") (pinfunction "1_1") (pintype "passive"))
      (node (ref "R99") (pin "2") (pinfunction "2_2") (pintype "passive"))
    )
    (net (code "39") (name "Net-(R100-Pad2)") (class "Default")
      (node (ref "R100") (pin "2") (pinfunction "2_2") (pintype "passive"))
      (node (ref "R92") (pin "1") (pinfunction "1_1") (pintype "passive"))
      (node (ref "R96") (pin "1") (pinfunction "1_1") (pintype "passive"))
    )
    (net (code "40") (name "V-POS5V") (class "Default")
      (node (ref "R103") (pin "2") (pinfunction "2_2") (pintype "passive"))
      (node (ref "R104") (pin "2") (pinfunction "2_2") (pintype "passive"))
      (node (ref "R61") (pin "2") (pinfunction "2_2") (pintype "passive"))
      (node (ref "R63") (pin "2") (pinfunction "2_2") (pintype "passive"))
      (node (ref "R65") (pin "2") (pinfunction "2_2") (pintype "passive"))
      (node (ref "R67") (pin "2") (pinfunction "2_2") (pintype "passive"))
      (node (ref "R81") (pin "2") (pinfunction "2_2") (pintype "passive"))
      (node (ref "R83") (pin "2") (pinfunction "2_2") (pintype "passive"))
      (node (ref "R85") (pin "2") (pinfunction "2_2") (pintype "passive"))
      (node (ref "R87") (pin "2") (pinfunction "2_2") (pintype "passive"))
    )
    (net (code "41") (name "V-POS24V") (class "Default")
      (node (ref "R62") (pin "2") (pinfunction "2_2") (pintype "passive"))
      (node (ref "R64") (pin "2") (pinfunction "2_2") (pintype "passive"))
      (node (ref "R66") (pin "2") (pinfunction "2_2") (pintype "passive"))
      (node (ref "R68") (pin "2") (pinfunction "2_2") (pintype "passive"))
      (node (ref "R82") (pin "2") (pinfunction "2_2") (pintype "passive"))
      (node (ref "R84") (pin "2") (pinfunction "2_2") (pintype "passive"))
      (node (ref "R86") (pin "2") (pinfunction "2_2") (pintype "passive"))
      (node (ref "R88") (pin "2") (pinfunction "2_2") (pintype "passive"))
    )
  )
)
